# ExtBoard.net
KiCad netlist of a schematic drawn in EAGLE
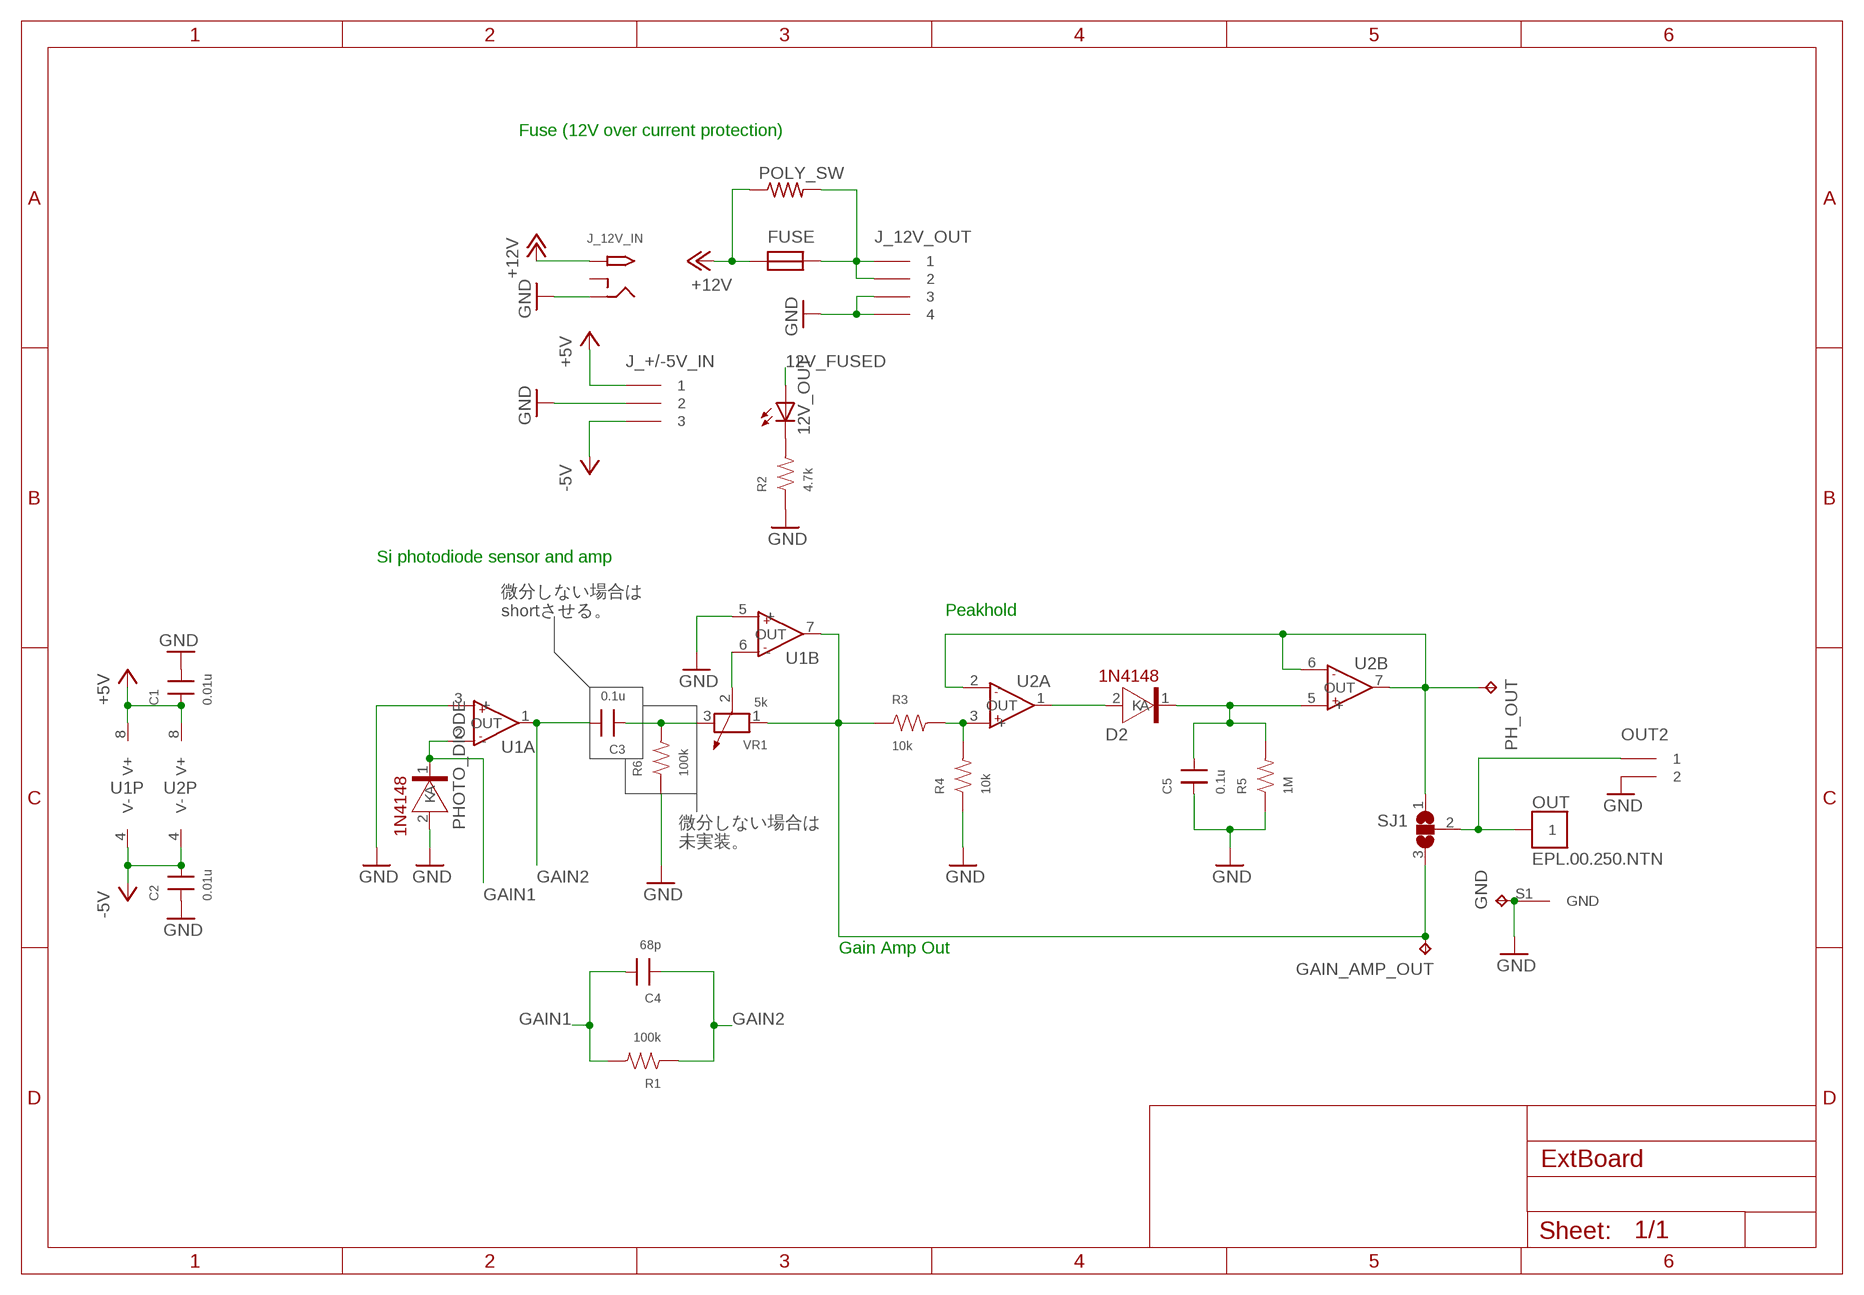
[diagram p0: schematic, sheet 1]

(export (version "E")
  (design (tool "Eeschema 10.0.6"))
  (components
    (comp (ref "12V_OUT")
      (value "LED_1608")
      (footprint "eagle-import:LED_1608")
      (libsource (lib "eagle-import") (part "LED_1608"))
    )
    (comp (ref "C1")
      (value "0.01u")
      (footprint "eagle-import:3216")
      (libsource (lib "eagle-import") (part "C226-3216"))
    )
    (comp (ref "C2")
      (value "0.01u")
      (footprint "eagle-import:3216")
      (libsource (lib "eagle-import") (part "C226-3216"))
    )
    (comp (ref "C3")
      (value "0.1u")
      (footprint "eagle-import:3216")
      (libsource (lib "eagle-import") (part "C226-3216"))
    )
    (comp (ref "C4")
      (value "68p")
      (footprint "eagle-import:3216")
      (libsource (lib "eagle-import") (part "C226-3216"))
    )
    (comp (ref "C5")
      (value "0.1u")
      (footprint "eagle-import:3216")
      (libsource (lib "eagle-import") (part "C226-3216"))
    )
    (comp (ref "D2")
      (value "1N4148")
      (footprint "eagle-import:4020-2P")
      (libsource (lib "eagle-import") (part "1N4148"))
    )
    (comp (ref "FUSE")
      (value "FUSE_LITTLEFUSE_649")
      (footprint "eagle-import:LITTLEFUSE_649")
      (libsource (lib "eagle-import") (part "FUSE_LITTLEFUSE_649"))
    )
    (comp (ref "GAIN_AMP_OUT")
      (value "TPPAD1-13")
      (footprint "eagle-import:P1-13")
      (libsource (lib "eagle-import") (part "TPPAD1-13"))
    )
    (comp (ref "GND")
      (value "TPPAD1-13")
      (footprint "eagle-import:P1-13")
      (libsource (lib "eagle-import") (part "TPPAD1-13"))
    )
    (comp (ref "J_+/-5V_IN")
      (value "IL-3P-S3EN2")
      (footprint "eagle-import:IL-3P-S3EN2")
      (libsource (lib "eagle-import") (part "IL-3P-S3EN2"))
    )
    (comp (ref "J_12V_IN")
      (value "2.1MMJACKTHM")
      (footprint "eagle-import:PJ-102A")
      (libsource (lib "eagle-import") (part "2.1MMJACKTHM"))
    )
    (comp (ref "J_12V_OUT")
      (value "IL-4P-S3EN2")
      (footprint "eagle-import:IL-4P-S3EN2")
      (libsource (lib "eagle-import") (part "IL-4P-S3EN2"))
    )
    (comp (ref "OUT")
      (value "EPL.00.250.NTN")
      (footprint "eagle-import:EPL.00.250.NTN")
      (libsource (lib "eagle-import") (part "EPL.00.250.NTN"))
    )
    (comp (ref "OUT2")
      (value "IL-2P-S3EN2")
      (footprint "eagle-import:IL-2P-S3EN2")
      (libsource (lib "eagle-import") (part "IL-2P-S3EN2"))
    )
    (comp (ref "PHOTO_DIODE")
      (value "1N4148")
      (footprint "eagle-import:4020-2P")
      (libsource (lib "eagle-import") (part "1N4148"))
    )
    (comp (ref "PH_OUT")
      (value "TPPAD1-13")
      (footprint "eagle-import:P1-13")
      (libsource (lib "eagle-import") (part "TPPAD1-13"))
    )
    (comp (ref "POLY_SW")
      (value "R-US_0207/10")
      (footprint "eagle-import:0207_10")
      (libsource (lib "eagle-import") (part "R-US_0207/10"))
    )
    (comp (ref "R1")
      (value "100k")
      (footprint "eagle-import:2012")
      (libsource (lib "eagle-import") (part "R2012"))
    )
    (comp (ref "R2")
      (value "4.7k")
      (footprint "eagle-import:2012")
      (libsource (lib "eagle-import") (part "R2012"))
    )
    (comp (ref "R3")
      (value "10k")
      (footprint "eagle-import:2012")
      (libsource (lib "eagle-import") (part "R2012"))
    )
    (comp (ref "R4")
      (value "10k")
      (footprint "eagle-import:2012")
      (libsource (lib "eagle-import") (part "R2012"))
    )
    (comp (ref "R5")
      (value "1M")
      (footprint "eagle-import:2012")
      (libsource (lib "eagle-import") (part "R2012"))
    )
    (comp (ref "R6")
      (value "100k")
      (footprint "eagle-import:2012")
      (libsource (lib "eagle-import") (part "R2012"))
    )
    (comp (ref "SJ1")
      (value "SJ2WW")
      (footprint "eagle-import:SJ_2W")
      (libsource (lib "eagle-import") (part "SJ2WW"))
    )
    (comp (ref "U1")
      (value "LM6172SOIC(D)8")
      (footprint "eagle-import:SOP8")
      (libsource (lib "eagle-import") (part "LM6172SOIC(D)8"))
    )
    (comp (ref "U2")
      (value "LM6172SOIC(D)8")
      (footprint "eagle-import:SOP8")
      (libsource (lib "eagle-import") (part "LM6172SOIC(D)8"))
    )
    (comp (ref "VR1")
      (value "5k")
      (footprint "eagle-import:ADJRP3-9.70XW5.0X9.80MM")
      (fields (field (name "MPN") "T93YA103KT20"))
      (libsource (lib "eagle-import") (part "DIP-TRIMMER-10K-10%-1/2W(3P-9.7X5.0X9.80MM)"))
    )
  )
  (nets
    (net (code "1") (name "+5V") (class "Default")
      (node (ref "C1") (pin "1") (pinfunction "1_1") (pintype "passive"))
      (node (ref "J_+/-5V_IN") (pin "P$1") (pinfunction "1_P$1") (pintype "bidirectional"))
      (node (ref "U1") (pin "8") (pinfunction "V+_8") (pintype "power_in"))
      (node (ref "U2") (pin "8") (pinfunction "V+_8") (pintype "power_in"))
    )
    (net (code "2") (name "+12V") (class "Default")
      (node (ref "FUSE") (pin "P$1") (pinfunction "P$1_P$1") (pintype "bidirectional"))
      (node (ref "J_12V_IN") (pin "TIP") (pinfunction "TIP_TIP") (pintype "bidirectional"))
      (node (ref "POLY_SW") (pin "1") (pinfunction "1_1") (pintype "passive"))
    )
    (net (code "3") (name "-5V") (class "Default")
      (node (ref "C2") (pin "2") (pinfunction "2_2") (pintype "passive"))
      (node (ref "J_+/-5V_IN") (pin "P$3") (pinfunction "3_P$3") (pintype "bidirectional"))
      (node (ref "U1") (pin "4") (pinfunction "V-_4") (pintype "power_in"))
      (node (ref "U2") (pin "4") (pinfunction "V-_4") (pintype "power_in"))
    )
    (net (code "4") (name "/12V_FUSED") (class "Default")
      (node (ref "12V_OUT") (pin "P$1") (pinfunction "A_P$1") (pintype "passive"))
      (node (ref "FUSE") (pin "P$2") (pinfunction "P$2_P$2") (pintype "bidirectional"))
      (node (ref "J_12V_OUT") (pin "P$1") (pinfunction "1_P$1") (pintype "bidirectional"))
      (node (ref "J_12V_OUT") (pin "P$2") (pinfunction "2_P$2") (pintype "bidirectional"))
      (node (ref "POLY_SW") (pin "2") (pinfunction "2_2") (pintype "passive"))
    )
    (net (code "5") (name "/GAIN1") (class "Default")
      (node (ref "C4") (pin "2") (pinfunction "2_2") (pintype "passive"))
      (node (ref "PHOTO_DIODE") (pin "1") (pinfunction "K_1") (pintype "passive"))
      (node (ref "R1") (pin "2") (pinfunction "2_2") (pintype "passive"))
      (node (ref "U1") (pin "2") (pinfunction "-_2") (pintype "input"))
    )
    (net (code "6") (name "/GAIN2") (class "Default")
      (node (ref "C3") (pin "2") (pinfunction "2_2") (pintype "passive"))
      (node (ref "C4") (pin "1") (pinfunction "1_1") (pintype "passive"))
      (node (ref "R1") (pin "1") (pinfunction "1_1") (pintype "passive"))
      (node (ref "U1") (pin "1") (pinfunction "OUT_1") (pintype "output"))
    )
    (net (code "7") (name "GND") (class "Default")
      (node (ref "C1") (pin "2") (pinfunction "2_2") (pintype "passive"))
      (node (ref "C2") (pin "1") (pinfunction "1_1") (pintype "passive"))
      (node (ref "C5") (pin "1") (pinfunction "1_1") (pintype "passive"))
      (node (ref "GND") (pin "TP") (pinfunction "TP_TP") (pintype "input"))
      (node (ref "J_+/-5V_IN") (pin "P$2") (pinfunction "2_P$2") (pintype "bidirectional"))
      (node (ref "J_12V_IN") (pin "RING") (pinfunction "RING_RING") (pintype "bidirectional"))
      (node (ref "J_12V_OUT") (pin "P$3") (pinfunction "3_P$3") (pintype "bidirectional"))
      (node (ref "J_12V_OUT") (pin "P$4") (pinfunction "4_P$4") (pintype "bidirectional"))
      (node (ref "OUT") (pin "S1") (pinfunction "GND_S1") (pintype "bidirectional"))
      (node (ref "OUT2") (pin "P$2") (pinfunction "2_P$2") (pintype "bidirectional"))
      (node (ref "PHOTO_DIODE") (pin "2") (pinfunction "A_2") (pintype "passive"))
      (node (ref "R2") (pin "1") (pinfunction "1_1") (pintype "passive"))
      (node (ref "R4") (pin "1") (pinfunction "1_1") (pintype "passive"))
      (node (ref "R5") (pin "1") (pinfunction "1_1") (pintype "passive"))
      (node (ref "R6") (pin "1") (pinfunction "1_1") (pintype "passive"))
      (node (ref "U1") (pin "3") (pinfunction "+_3") (pintype "input"))
      (node (ref "U1") (pin "5") (pinfunction "+_5") (pintype "input"))
    )
    (net (code "8") (name "Net-(12V_OUT-C)") (class "Default")
      (node (ref "12V_OUT") (pin "P$2") (pinfunction "C_P$2") (pintype "passive"))
      (node (ref "R2") (pin "2") (pinfunction "2_2") (pintype "passive"))
    )
    (net (code "9") (name "Net-(C3-Pad1)") (class "Default")
      (node (ref "C3") (pin "1") (pinfunction "1_1") (pintype "passive"))
      (node (ref "R6") (pin "2") (pinfunction "2_2") (pintype "passive"))
      (node (ref "VR1") (pin "3") (pinfunction "3_3") (pintype "passive"))
    )
    (net (code "10") (name "Net-(D2-A)") (class "Default")
      (node (ref "D2") (pin "2") (pinfunction "A_2") (pintype "passive"))
      (node (ref "U2") (pin "1") (pinfunction "OUT_1") (pintype "output"))
    )
    (net (code "11") (name "Net-(D2-K)") (class "Default")
      (node (ref "C5") (pin "2") (pinfunction "2_2") (pintype "passive"))
      (node (ref "D2") (pin "1") (pinfunction "K_1") (pintype "passive"))
      (node (ref "R5") (pin "2") (pinfunction "2_2") (pintype "passive"))
      (node (ref "U2") (pin "5") (pinfunction "+_5") (pintype "input"))
    )
    (net (code "12") (name "Net-(OUT2-1)") (class "Default")
      (node (ref "OUT") (pin "1") (pinfunction "1_1") (pintype "passive"))
      (node (ref "OUT2") (pin "P$1") (pinfunction "1_P$1") (pintype "bidirectional"))
      (node (ref "SJ1") (pin "2") (pinfunction "2_2") (pintype "passive"))
    )
    (net (code "13") (name "Net-(U1B--)") (class "Default")
      (node (ref "U1") (pin "6") (pinfunction "-_6") (pintype "input"))
      (node (ref "VR1") (pin "2") (pinfunction "2_2") (pintype "passive"))
    )
    (net (code "14") (name "Net-(U1B-OUT)") (class "Default")
      (node (ref "GAIN_AMP_OUT") (pin "TP") (pinfunction "TP_TP") (pintype "input"))
      (node (ref "R3") (pin "1") (pinfunction "1_1") (pintype "passive"))
      (node (ref "SJ1") (pin "3") (pinfunction "3_3") (pintype "passive"))
      (node (ref "U1") (pin "7") (pinfunction "OUT_7") (pintype "output"))
      (node (ref "VR1") (pin "1") (pinfunction "1_1") (pintype "passive"))
    )
    (net (code "15") (name "Net-(U2A-+)") (class "Default")
      (node (ref "R3") (pin "2") (pinfunction "2_2") (pintype "passive"))
      (node (ref "R4") (pin "2") (pinfunction "2_2") (pintype "passive"))
      (node (ref "U2") (pin "3") (pinfunction "+_3") (pintype "input"))
    )
    (net (code "16") (name "Net-(U2A--)") (class "Default")
      (node (ref "PH_OUT") (pin "TP") (pinfunction "TP_TP") (pintype "input"))
      (node (ref "SJ1") (pin "1") (pinfunction "1_1") (pintype "passive"))
      (node (ref "U2") (pin "2") (pinfunction "-_2") (pintype "input"))
      (node (ref "U2") (pin "6") (pinfunction "-_6") (pintype "input"))
      (node (ref "U2") (pin "7") (pinfunction "OUT_7") (pintype "output"))
    )
    (net (code "17") (name "unconnected-(J_12V_IN-PadRING_SW)") (class "Default")
      (node (ref "J_12V_IN") (pin "RING_SW") (pinfunction "RING_SW_RING_SW") (pintype "bidirectional"))
    )
  )
)
